# SUP_2_5_FMC.net
KiCad netlist of a schematic drawn in Altium Designer
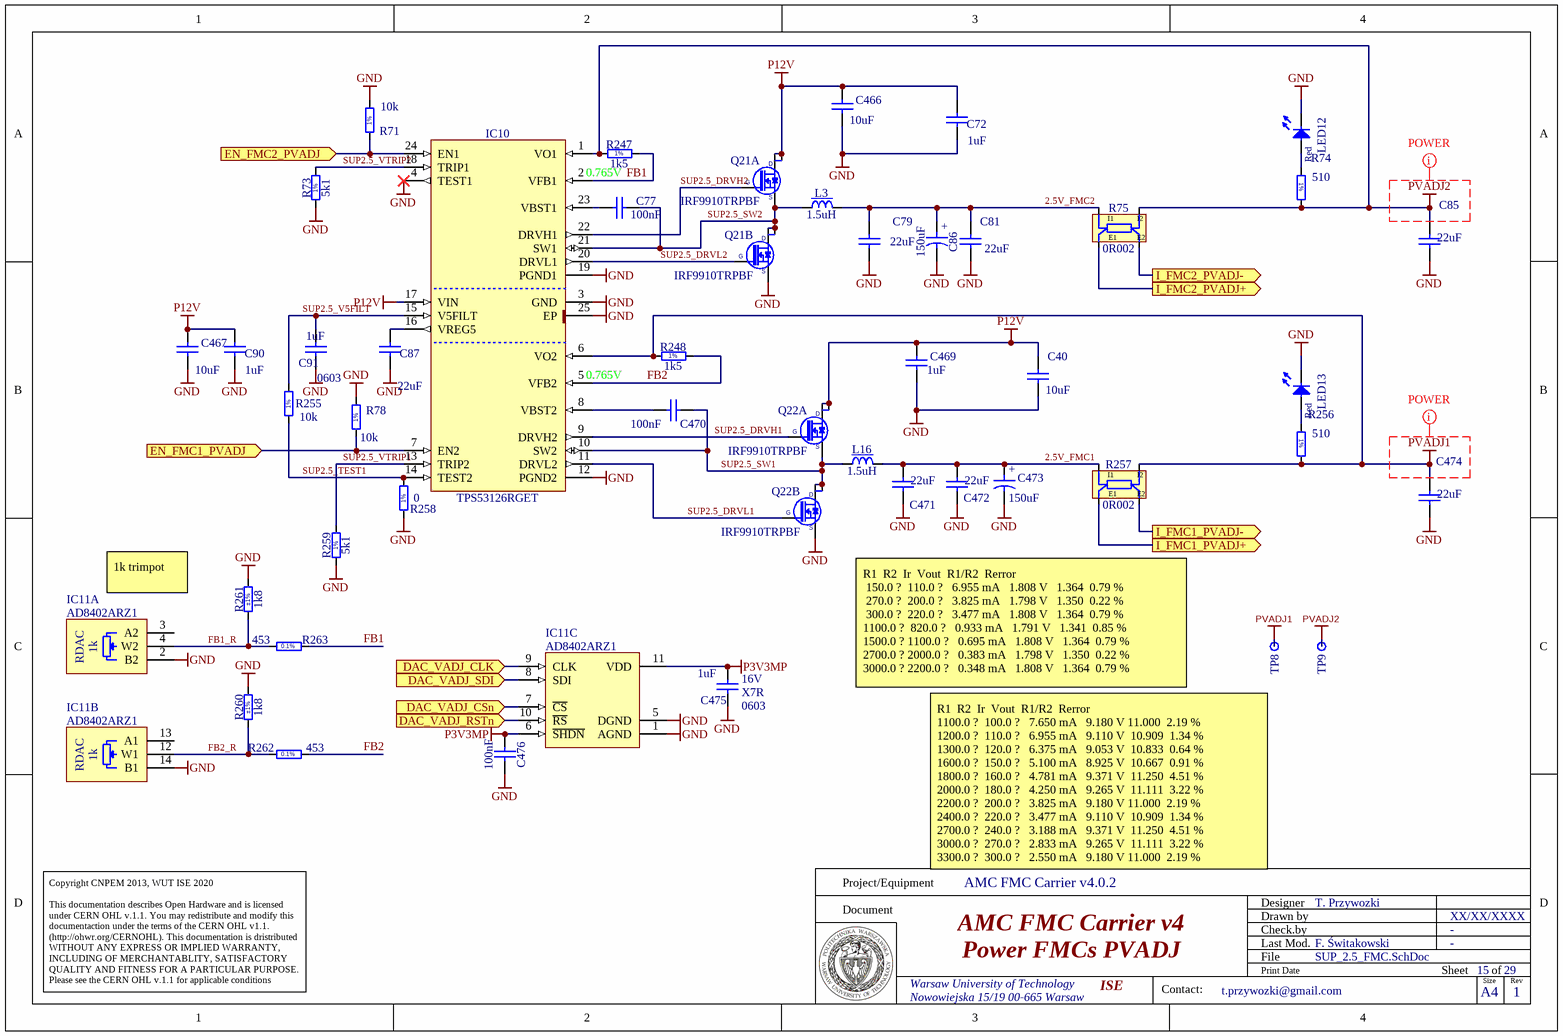
[diagram p0: SUP_2.5_FMC.SchDoc]

(export (version "E")
  (design (tool "Eeschema 10.0.6"))
  (components
    (comp (ref "C40")
      (value "10uF")
      (footprint "CAPC2012X135N")
      (description "Non-polarised capacitor")
      (fields
        (field (name "PART NUMBER") "CC0805_10UF_16V_10%_X5R")
        (field (name "VOLTAGE") "16V")
        (field (name "AUTHOR") "CERN DEM JLC")
      )
      (libsource (lib "Capacitors") (part "Capacitor - non polarized"))
    )
    (comp (ref "C72")
      (value "1uF")
      (footprint "CAPC1608X87N")
      (description "Non-polarised capacitor")
      (fields
        (field (name "PART NUMBER") "CC0603_1UF_16V_10%_X7R")
        (field (name "VOLTAGE") "16V")
        (field (name "AUTHOR") "CERN DEM JLC")
      )
      (libsource (lib "Capacitors") (part "Capacitor - non polarized"))
    )
    (comp (ref "C77")
      (value "100nF")
      (footprint "CAPC1005X55N")
      (description "Non-polarised capacitor")
      (fields
        (field (name "PART NUMBER") "CC0402_100NF_16V_10%_X7R")
        (field (name "VOLTAGE") "16V")
        (field (name "AUTHOR") "CERN DEM JLC")
      )
      (libsource (lib "Capacitors") (part "Capacitor - non polarized"))
    )
    (comp (ref "C79")
      (value "22uF")
      (footprint "CAPC3216X180N")
      (description "Non-polarised capacitor")
      (fields
        (field (name "PART NUMBER") "CC1206_22UF_10V_10%_X7R")
        (field (name "VOLTAGE") "10V")
        (field (name "AUTHOR") "CERN DEM JLC")
      )
      (libsource (lib "Capacitors") (part "Capacitor - non polarized"))
    )
    (comp (ref "C81")
      (value "22uF")
      (footprint "CAPC3216X180N")
      (description "Non-polarised capacitor")
      (fields
        (field (name "PART NUMBER") "CC1206_22UF_10V_10%_X7R")
        (field (name "VOLTAGE") "10V")
        (field (name "AUTHOR") "CERN DEM JLC")
      )
      (libsource (lib "Capacitors") (part "Capacitor - non polarized"))
    )
    (comp (ref "C85")
      (value "22uF")
      (footprint "CAPC3216X180N")
      (description "Non-polarised capacitor")
      (fields
        (field (name "PART NUMBER") "CC1206_22UF_10V_10%_X7R")
        (field (name "VOLTAGE") "10V")
        (field (name "AUTHOR") "CERN DEM JLC")
      )
      (libsource (lib "Capacitors") (part "Capacitor - non polarized"))
    )
    (comp (ref "C86")
      (value "150uF")
      (footprint "CAPMP7343X200N")
      (description "Polarised capacitor")
      (fields
        (field (name "PART NUMBER") "CAEM7343-20_150UF_4V_20%_LESR0016")
        (field (name "VOLTAGE") "4V")
        (field (name "AUTHOR") "CERN DEM JLC")
      )
      (libsource (lib "Capacitors") (part "Capacitor - polarized"))
    )
    (comp (ref "C87")
      (value "22uF")
      (footprint "CAPC3216X180N")
      (description "Non-polarised capacitor")
      (fields
        (field (name "PART NUMBER") "CC1206_22UF_10V_10%_X7R")
        (field (name "VOLTAGE") "10V")
        (field (name "AUTHOR") "CERN DEM JLC")
      )
      (libsource (lib "Capacitors") (part "Capacitor - non polarized"))
    )
    (comp (ref "C90")
      (value "1uF")
      (footprint "CAPC1608X87N")
      (description "Non-polarised capacitor")
      (fields
        (field (name "PART NUMBER") "CC0603_1UF_16V_10%_X7R")
        (field (name "VOLTAGE") "16V")
        (field (name "AUTHOR") "CERN DEM JLC")
      )
      (libsource (lib "Capacitors") (part "Capacitor - non polarized"))
    )
    (comp (ref "C91")
      (value "1uF")
      (footprint "CAPC1608X87N")
      (description "Non-polarised capacitor")
      (fields
        (field (name "PART NUMBER") "CC0603_1UF_16V_10%_X7R")
        (field (name "VOLTAGE") "16V")
        (field (name "CASE") "0603")
        (field (name "AUTHOR") "CERN DEM JLC")
      )
      (libsource (lib "Capacitors") (part "Capacitor - non polarized"))
    )
    (comp (ref "C466")
      (value "10uF")
      (footprint "CAPC2012X135N")
      (description "Non-polarised capacitor")
      (fields
        (field (name "PART NUMBER") "CC0805_10UF_16V_10%_X5R")
        (field (name "VOLTAGE") "16V")
        (field (name "AUTHOR") "CERN DEM JLC")
      )
      (libsource (lib "Capacitors") (part "Capacitor - non polarized"))
    )
    (comp (ref "C467")
      (value "10uF")
      (footprint "CAPC2012X135N")
      (description "Non-polarised capacitor")
      (fields
        (field (name "PART NUMBER") "CC0805_10UF_16V_10%_X5R")
        (field (name "VOLTAGE") "16V")
        (field (name "AUTHOR") "CERN DEM JLC")
      )
      (libsource (lib "Capacitors") (part "Capacitor - non polarized"))
    )
    (comp (ref "C469")
      (value "1uF")
      (footprint "CAPC1608X87N")
      (description "Non-polarised capacitor")
      (fields
        (field (name "PART NUMBER") "CC0603_1UF_16V_10%_X7R")
        (field (name "VOLTAGE") "16V")
        (field (name "AUTHOR") "CERN DEM JLC")
      )
      (libsource (lib "Capacitors") (part "Capacitor - non polarized"))
    )
    (comp (ref "C470")
      (value "100nF")
      (footprint "CAPC1005X55N")
      (description "Non-polarised capacitor")
      (fields
        (field (name "PART NUMBER") "CC0402_100NF_16V_10%_X7R")
        (field (name "VOLTAGE") "16V")
        (field (name "AUTHOR") "CERN DEM JLC")
      )
      (libsource (lib "Capacitors") (part "Capacitor - non polarized"))
    )
    (comp (ref "C471")
      (value "22uF")
      (footprint "CAPC3216X180N")
      (description "Non-polarised capacitor")
      (fields
        (field (name "PART NUMBER") "CC1206_22UF_10V_10%_X7R")
        (field (name "VOLTAGE") "10V")
        (field (name "AUTHOR") "CERN DEM JLC")
      )
      (libsource (lib "Capacitors") (part "Capacitor - non polarized"))
    )
    (comp (ref "C472")
      (value "22uF")
      (footprint "CAPC3216X180N")
      (description "Non-polarised capacitor")
      (fields
        (field (name "PART NUMBER") "CC1206_22UF_10V_10%_X7R")
        (field (name "VOLTAGE") "10V")
        (field (name "AUTHOR") "CERN DEM JLC")
      )
      (libsource (lib "Capacitors") (part "Capacitor - non polarized"))
    )
    (comp (ref "C473")
      (value "150uF")
      (footprint "CAPMP7343X200N")
      (description "Polarised capacitor")
      (fields
        (field (name "PART NUMBER") "CAEM7343-20_150UF_4V_20%_LESR0016")
        (field (name "VOLTAGE") "4V")
        (field (name "AUTHOR") "CERN DEM JLC")
      )
      (libsource (lib "Capacitors") (part "Capacitor - polarized"))
    )
    (comp (ref "C474")
      (value "22uF")
      (footprint "CAPC3216X180N")
      (description "Non-polarised capacitor")
      (fields
        (field (name "PART NUMBER") "CC1206_22UF_10V_10%_X7R")
        (field (name "VOLTAGE") "10V")
        (field (name "AUTHOR") "CERN DEM JLC")
      )
      (libsource (lib "Capacitors") (part "Capacitor - non polarized"))
    )
    (comp (ref "C475")
      (value "1uF")
      (footprint "CAPC1608X87N")
      (description "Non-polarised capacitor")
      (fields
        (field (name "PART NUMBER") "CC0603_1UF_16V_10%_X7R")
        (field (name "VOLTAGE") "16V")
        (field (name "TC") "X7R")
        (field (name "TOLERANCE") "±10%")
        (field (name "CASE") "0603")
        (field (name "AUTHOR") "CERN DEM JLC")
      )
      (libsource (lib "Capacitors") (part "Capacitor - non polarized"))
    )
    (comp (ref "C476")
      (value "100nF")
      (footprint "CAPC0603X33N")
      (description "Non-polarised capacitor")
      (fields
        (field (name "PART NUMBER") "CC0201_100NF_6.3V_10%_X5R")
        (field (name "VOLTAGE") "6.3V")
        (field (name "AUTHOR") "CERN DEM JLC")
      )
      (libsource (lib "Capacitors") (part "Capacitor - non polarized"))
    )
    (comp (ref "IC10")
      (value "TPS53126RGET")
      (footprint "QFN50P400X400X100-25N-S255")
      (description "Dual Synchronous Step-Down Controller For Low Voltage Power Rails")
      (fields (field (name "MANUFACTURER") "TEXAS INSTRUMENTS") (field (name "AUTHOR") "CERN DEM JLC"))
      (libsource (lib "ICs And Semiconductors") (part "TPS53126RGET"))
    )
    (comp (ref "IC11")
      (value "AD8402ARZ1")
      (footprint "SOIC127P600X175-14N")
      (description "2-Channel 1k Digital Potentiometer")
      (fields (field (name "MANUFACTURER") "ANALOG DEVICES") (field (name "AUTHOR") "CERN DEM JLC"))
      (libsource (lib "ICs And Semiconductors") (part "AD8402ARZ1"))
    )
    (comp (ref "L3")
      (value "1.5uH")
      (footprint "IND_TDK_SPM6530")
      (description "Inductor With Core")
      (fields
        (field (name "PART NUMBER") "IND_1.5UH_20%_TDK_SPM6530")
        (field (name "POWER") "11A")
        (field (name "AUTHOR") "CERN DEM MR")
      )
      (libsource (lib "Inductors & Transformers") (part "Inductor With Magnetic core"))
    )
    (comp (ref "L16")
      (value "1.5uH")
      (footprint "IND_TDK_SPM6530")
      (description "Inductor With Core")
      (fields
        (field (name "PART NUMBER") "IND_1.5UH_20%_TDK_SPM6530")
        (field (name "POWER") "11A")
        (field (name "AUTHOR") "CERN DEM MR")
      )
      (libsource (lib "Inductors & Transformers") (part "Inductor With Magnetic core"))
    )
    (comp (ref "LED12")
      (value "Red")
      (footprint "LED_KINGBRIGHT_KPH-1608SURCK")
      (description "LED Red 1C 2A")
      (fields
        (field (name "PART NUMBER") "LED_KINGBRIGHT_KPH-1608SURCK")
        (field (name "MANUFACTURER") "KINGBRIGHT")
        (field (name "AUTHOR") "CERN DEM JLC")
      )
      (libsource (lib "ICs And Semiconductors") (part "LED Red 1C 2A"))
    )
    (comp (ref "LED13")
      (value "Red")
      (footprint "LED_KINGBRIGHT_KPH-1608SURCK")
      (description "LED Red 1C 2A")
      (fields
        (field (name "PART NUMBER") "LED_KINGBRIGHT_KPH-1608SURCK")
        (field (name "MANUFACTURER") "KINGBRIGHT")
        (field (name "AUTHOR") "CERN DEM JLC")
      )
      (libsource (lib "ICs And Semiconductors") (part "LED Red 1C 2A"))
    )
    (comp (ref "Q21")
      (value "IRF9910TRPBF")
      (footprint "SOIC127P600X175-8N")
      (description "Dual SO-8 MOSFET For POL Cconverter")
      (fields (field (name "MANUFACTURER") "INTERNATIONAL RECTIFIER") (field (name "AUTHOR") "TP"))
      (libsource (lib "AMC_FMC_Carrier") (part "IRF9910"))
    )
    (comp (ref "Q22")
      (value "IRF9910TRPBF")
      (footprint "SOIC127P600X175-8N")
      (description "Dual SO-8 MOSFET For POL Cconverter")
      (fields (field (name "MANUFACTURER") "INTERNATIONAL RECTIFIER") (field (name "AUTHOR") "TP"))
      (libsource (lib "AMC_FMC_Carrier") (part "IRF9910"))
    )
    (comp (ref "R71")
      (value "10k")
      (footprint "RESC1005X40N")
      (description "Resistor - 1%")
      (fields
        (field (name "PART NUMBER") "R0402_10K_1%_0.0625W_100PPM")
        (field (name "POWER") "0.0625W")
        (field (name "AUTHOR") "CERN DEM JLC")
      )
      (libsource (lib "Resistors") (part "Resistor - 1%"))
    )
    (comp (ref "R73")
      (value "5k1")
      (footprint "RESC1608X55N")
      (description "Resistor - 1%")
      (fields
        (field (name "PART NUMBER") "R0603_5K1_1%_0.1W_100PPM")
        (field (name "POWER") "0.1W")
        (field (name "AUTHOR") "CERN DEM JLC")
      )
      (libsource (lib "Resistors") (part "Resistor - 1%"))
    )
    (comp (ref "R74")
      (value "510")
      (footprint "RESC1005X40N")
      (description "Resistor - 1%")
      (fields
        (field (name "PART NUMBER") "R0402_510R_1%_0.0625W_100PPM")
        (field (name "POWER") "0.0625W")
        (field (name "AUTHOR") "CERN DEM JLC")
      )
      (libsource (lib "Resistors") (part "Resistor - 1%"))
    )
    (comp (ref "R75")
      (value "0R002")
      (footprint "RES_VISHAY_WSK2512_0R005-0R2")
      (description "Power and Current Sensing Resistor")
      (fields
        (field (name "PART NUMBER") "R2512_0R002_1%_1W_35PPM_VISHAY_WSK")
        (field (name "POWER") "1W")
        (field (name "AUTHOR") "CERN DEM MR")
      )
      (libsource (lib "Resistors") (part "Current Sense Resistor"))
    )
    (comp (ref "R78")
      (value "10k")
      (footprint "RESC1005X40N")
      (description "Resistor - 1%")
      (fields
        (field (name "PART NUMBER") "R0402_10K_1%_0.0625W_100PPM")
        (field (name "POWER") "0.0625W")
        (field (name "AUTHOR") "CERN DEM JLC")
      )
      (libsource (lib "Resistors") (part "Resistor - 1%"))
    )
    (comp (ref "R247")
      (value "1k5")
      (footprint "RESC1608X55N")
      (description "Resistor - 1%")
      (fields
        (field (name "PART NUMBER") "R0603_1K5_1%_0.1W_100PPM")
        (field (name "POWER") "0.1W")
        (field (name "AUTHOR") "CERN DEM JLC")
      )
      (libsource (lib "Resistors") (part "Resistor - 1%"))
    )
    (comp (ref "R248")
      (value "1k5")
      (footprint "RESC1608X55N")
      (description "Resistor - 1%")
      (fields
        (field (name "PART NUMBER") "R0603_1K5_1%_0.1W_100PPM")
        (field (name "POWER") "0.1W")
        (field (name "AUTHOR") "CERN DEM JLC")
      )
      (libsource (lib "Resistors") (part "Resistor - 1%"))
    )
    (comp (ref "R255")
      (value "10k")
      (footprint "RESC1005X40N")
      (description "Resistor - 1%")
      (fields
        (field (name "PART NUMBER") "R0402_10K_1%_0.0625W_100PPM")
        (field (name "POWER") "0.0625W")
        (field (name "AUTHOR") "CERN DEM JLC")
      )
      (libsource (lib "Resistors") (part "Resistor - 1%"))
    )
    (comp (ref "R256")
      (value "510")
      (footprint "RESC1005X40N")
      (description "Resistor - 1%")
      (fields
        (field (name "PART NUMBER") "R0402_510R_1%_0.0625W_100PPM")
        (field (name "POWER") "0.0625W")
        (field (name "AUTHOR") "CERN DEM JLC")
      )
      (libsource (lib "Resistors") (part "Resistor - 1%"))
    )
    (comp (ref "R257")
      (value "0R002")
      (footprint "RES_VISHAY_WSK2512_0R005-0R2")
      (description "Power and Current Sensing Resistor")
      (fields
        (field (name "PART NUMBER") "R2512_0R002_1%_1W_35PPM_VISHAY_WSK")
        (field (name "POWER") "1W")
        (field (name "AUTHOR") "CERN DEM MR")
      )
      (libsource (lib "Resistors") (part "Current Sense Resistor"))
    )
    (comp (ref "R258")
      (value "0")
      (footprint "RESC1005X40N")
      (description "Resistor - 1%")
      (fields
        (field (name "PART NUMBER") "R0402_0R_JUMPER")
        (field (name "MANUFACTURER") "GENERIC")
        (field (name "AUTHOR") "CERN DEM JLC")
      )
      (libsource (lib "Resistors") (part "Resistor - 1%"))
    )
    (comp (ref "R259")
      (value "5k1")
      (footprint "RESC1608X55N")
      (description "Resistor - 1%")
      (fields
        (field (name "PART NUMBER") "R0603_5K1_1%_0.1W_100PPM")
        (field (name "POWER") "0.1W")
        (field (name "AUTHOR") "CERN DEM JLC")
      )
      (libsource (lib "Resistors") (part "Resistor - 1%"))
    )
    (comp (ref "R260")
      (value "1k8")
      (footprint "RESC1608X55N")
      (description "Resistor - 1%")
      (fields
        (field (name "TOLERANCE") "±1%")
        (field (name "PART NUMBER") "R0603_1K8_1%_0.1W_100PPM")
        (field (name "POWER") "0.1W")
        (field (name "AUTHOR") "CERN DEM JLC")
      )
      (libsource (lib "Resistors") (part "Resistor - 1%"))
    )
    (comp (ref "R261")
      (value "1k8")
      (footprint "RESC1608X55N")
      (description "Resistor - 1%")
      (fields
        (field (name "TOLERANCE") "±1%")
        (field (name "PART NUMBER") "R0603_1K8_1%_0.1W_100PPM")
        (field (name "POWER") "0.1W")
        (field (name "AUTHOR") "CERN DEM JLC")
      )
      (libsource (lib "Resistors") (part "Resistor - 1%"))
    )
    (comp (ref "R262")
      (value "453")
      (footprint "RESC1608X55N")
      (description "Resistor - 0.1%")
      (fields
        (field (name "PART NUMBER") "R0603_453R_0.1%_0.063W_10PPM")
        (field (name "POWER") "0.063W")
        (field (name "AUTHOR") "CERN DEM JLC")
      )
      (libsource (lib "Resistors") (part "Resistor - 0.1%"))
    )
    (comp (ref "R263")
      (value "453")
      (footprint "RESC1608X55N")
      (description "Resistor - 0.1%")
      (fields
        (field (name "PART NUMBER") "R0603_453R_0.1%_0.063W_10PPM")
        (field (name "POWER") "0.063W")
        (field (name "AUTHOR") "CERN DEM JLC")
      )
      (libsource (lib "Resistors") (part "Resistor - 0.1%"))
    )
    (comp (ref "TP8")
      (value "Test Point")
      (footprint "TPS127")
      (fields (field (name "PART NUMBER") "SMD_PAD_1.27X1.27MM") (field (name "AUTHOR") "CERN DEM JLC"))
      (libsource (lib "Eletro-mechanical") (part "Test Point"))
    )
    (comp (ref "TP9")
      (value "Test Point")
      (footprint "TPS127")
      (fields (field (name "PART NUMBER") "SMD_PAD_1.27X1.27MM") (field (name "AUTHOR") "CERN DEM JLC"))
      (libsource (lib "Eletro-mechanical") (part "Test Point"))
    )
  )
  (nets
    (net (code "1") (name "/2.5V_FMC1") (class "Default")
      (node (ref "C471") (pin "1") (pinfunction "1_1") (pintype "passive"))
      (node (ref "C472") (pin "1") (pinfunction "1_1") (pintype "passive"))
      (node (ref "C473") (pin "1") (pinfunction "1_1") (pintype "passive"))
      (node (ref "L16") (pin "2") (pinfunction "2_2") (pintype "passive"))
      (node (ref "R257") (pin "I1") (pinfunction "I1_I1") (pintype "passive"))
    )
    (net (code "2") (name "/2.5V_FMC2") (class "Default")
      (node (ref "C79") (pin "1") (pinfunction "1_1") (pintype "passive"))
      (node (ref "C81") (pin "1") (pinfunction "1_1") (pintype "passive"))
      (node (ref "C86") (pin "1") (pinfunction "1_1") (pintype "passive"))
      (node (ref "L3") (pin "2") (pinfunction "2_2") (pintype "passive"))
      (node (ref "R75") (pin "I1") (pinfunction "I1_I1") (pintype "passive"))
    )
    (net (code "3") (name "/DAC_VADJ_CLK") (class "Default")
      (node (ref "IC11") (pin "9") (pinfunction "CLK_9") (pintype "input"))
    )
    (net (code "4") (name "/DAC_VADJ_CSn") (class "Default")
      (node (ref "IC11") (pin "7") (pinfunction "~{CS}_7") (pintype "input"))
    )
    (net (code "5") (name "/DAC_VADJ_RSTn") (class "Default")
      (node (ref "IC11") (pin "10") (pinfunction "~{RS}_10") (pintype "input"))
    )
    (net (code "6") (name "/DAC_VADJ_SDI") (class "Default")
      (node (ref "IC11") (pin "8") (pinfunction "SDI_8") (pintype "input"))
    )
    (net (code "7") (name "/EN_FMC1_PVADJ") (class "Default")
      (node (ref "IC10") (pin "7") (pinfunction "EN2_7") (pintype "input"))
      (node (ref "R78") (pin "1") (pinfunction "1_1") (pintype "passive"))
    )
    (net (code "8") (name "/EN_FMC2_PVADJ") (class "Default")
      (node (ref "IC10") (pin "24") (pinfunction "EN1_24") (pintype "input"))
      (node (ref "R71") (pin "1") (pinfunction "1_1") (pintype "passive"))
    )
    (net (code "9") (name "/FB1") (class "Default")
      (node (ref "IC10") (pin "2") (pinfunction "VFB1_2") (pintype "input"))
      (node (ref "R247") (pin "2") (pinfunction "2_2") (pintype "passive"))
      (node (ref "R263") (pin "1") (pinfunction "1_1") (pintype "passive"))
    )
    (net (code "10") (name "/FB1_R") (class "Default")
      (node (ref "IC11") (pin "4") (pinfunction "W2_4") (pintype "passive"))
      (node (ref "R261") (pin "1") (pinfunction "1_1") (pintype "passive"))
      (node (ref "R263") (pin "2") (pinfunction "2_2") (pintype "passive"))
    )
    (net (code "11") (name "/FB2") (class "Default")
      (node (ref "IC10") (pin "5") (pinfunction "VFB2_5") (pintype "input"))
      (node (ref "R248") (pin "2") (pinfunction "2_2") (pintype "passive"))
      (node (ref "R262") (pin "2") (pinfunction "2_2") (pintype "passive"))
    )
    (net (code "12") (name "/FB2_R") (class "Default")
      (node (ref "IC11") (pin "12") (pinfunction "W1_12") (pintype "passive"))
      (node (ref "R260") (pin "1") (pinfunction "1_1") (pintype "passive"))
      (node (ref "R262") (pin "1") (pinfunction "1_1") (pintype "passive"))
    )
    (net (code "13") (name "/I_FMC1_PVADJ+") (class "Default")
      (node (ref "R257") (pin "E1") (pinfunction "E1_E1") (pintype "passive"))
    )
    (net (code "14") (name "/I_FMC1_PVADJ-") (class "Default")
      (node (ref "R257") (pin "E2") (pinfunction "E2_E2") (pintype "passive"))
    )
    (net (code "15") (name "/I_FMC2_PVADJ+") (class "Default")
      (node (ref "R75") (pin "E1") (pinfunction "E1_E1") (pintype "passive"))
    )
    (net (code "16") (name "/I_FMC2_PVADJ-") (class "Default")
      (node (ref "R75") (pin "E2") (pinfunction "E2_E2") (pintype "passive"))
    )
    (net (code "17") (name "/SUP2.5_DRVH1") (class "Default")
      (node (ref "IC10") (pin "9") (pinfunction "DRVH2_9") (pintype "output"))
      (node (ref "Q22") (pin "4") (pinfunction "G_4") (pintype "passive"))
    )
    (net (code "18") (name "/SUP2.5_DRVH2") (class "Default")
      (node (ref "IC10") (pin "22") (pinfunction "DRVH1_22") (pintype "output"))
      (node (ref "Q21") (pin "4") (pinfunction "G_4") (pintype "passive"))
    )
    (net (code "19") (name "/SUP2.5_DRVL1") (class "Default")
      (node (ref "IC10") (pin "11") (pinfunction "DRVL2_11") (pintype "output"))
      (node (ref "Q22") (pin "2") (pinfunction "G_2") (pintype "passive"))
    )
    (net (code "20") (name "/SUP2.5_DRVL2") (class "Default")
      (node (ref "IC10") (pin "20") (pinfunction "DRVL1_20") (pintype "output"))
      (node (ref "Q21") (pin "2") (pinfunction "G_2") (pintype "passive"))
    )
    (net (code "21") (name "/SUP2.5_SW1") (class "Default")
      (node (ref "C470") (pin "1") (pinfunction "1_1") (pintype "passive"))
      (node (ref "IC10") (pin "10") (pinfunction "SW2_10") (pintype "bidirectional"))
      (node (ref "L16") (pin "1") (pinfunction "1_1") (pintype "passive"))
      (node (ref "Q22") (pin "3") (pinfunction "S_3") (pintype "passive"))
      (node (ref "Q22") (pin "7") (pinfunction "D_7") (pintype "passive"))
      (node (ref "Q22") (pin "8") (pinfunction "D_8") (pintype "passive"))
    )
    (net (code "22") (name "/SUP2.5_SW2") (class "Default")
      (node (ref "C77") (pin "1") (pinfunction "1_1") (pintype "passive"))
      (node (ref "IC10") (pin "21") (pinfunction "SW1_21") (pintype "bidirectional"))
      (node (ref "L3") (pin "1") (pinfunction "1_1") (pintype "passive"))
      (node (ref "Q21") (pin "3") (pinfunction "S_3") (pintype "passive"))
      (node (ref "Q21") (pin "7") (pinfunction "D_7") (pintype "passive"))
      (node (ref "Q21") (pin "8") (pinfunction "D_8") (pintype "passive"))
    )
    (net (code "23") (name "/SUP2.5_TEST1") (class "Default")
      (node (ref "IC10") (pin "14") (pinfunction "TEST2_14") (pintype "input"))
      (node (ref "R255") (pin "1") (pinfunction "1_1") (pintype "passive"))
      (node (ref "R258") (pin "2") (pinfunction "2_2") (pintype "passive"))
    )
    (net (code "24") (name "/SUP2.5_V5FILT") (class "Default")
      (node (ref "C91") (pin "2") (pinfunction "2_2") (pintype "passive"))
      (node (ref "IC10") (pin "15") (pinfunction "V5FILT_15") (pintype "input"))
      (node (ref "R255") (pin "2") (pinfunction "2_2") (pintype "passive"))
    )
    (net (code "25") (name "/SUP2.5_VTRIP1") (class "Default")
      (node (ref "IC10") (pin "13") (pinfunction "TRIP2_13") (pintype "input"))
      (node (ref "R259") (pin "2") (pinfunction "2_2") (pintype "passive"))
    )
    (net (code "26") (name "/SUP2.5_VTRIP2") (class "Default")
      (node (ref "IC10") (pin "18") (pinfunction "TRIP1_18") (pintype "input"))
      (node (ref "R73") (pin "2") (pinfunction "2_2") (pintype "passive"))
    )
    (net (code "27") (name "GND") (class "Default")
      (node (ref "C40") (pin "1") (pinfunction "1_1") (pintype "passive"))
      (node (ref "C466") (pin "1") (pinfunction "1_1") (pintype "passive"))
      (node (ref "C467") (pin "1") (pinfunction "1_1") (pintype "passive"))
      (node (ref "C469") (pin "1") (pinfunction "1_1") (pintype "passive"))
      (node (ref "C471") (pin "2") (pinfunction "2_2") (pintype "passive"))
      (node (ref "C472") (pin "2") (pinfunction "2_2") (pintype "passive"))
      (node (ref "C473") (pin "2") (pinfunction "2_2") (pintype "passive"))
      (node (ref "C474") (pin "2") (pinfunction "2_2") (pintype "passive"))
      (node (ref "C475") (pin "1") (pinfunction "1_1") (pintype "passive"))
      (node (ref "C476") (pin "2") (pinfunction "2_2") (pintype "passive"))
      (node (ref "C72") (pin "1") (pinfunction "1_1") (pintype "passive"))
      (node (ref "C79") (pin "2") (pinfunction "2_2") (pintype "passive"))
      (node (ref "C81") (pin "2") (pinfunction "2_2") (pintype "passive"))
      (node (ref "C85") (pin "2") (pinfunction "2_2") (pintype "passive"))
      (node (ref "C86") (pin "2") (pinfunction "2_2") (pintype "passive"))
      (node (ref "C87") (pin "1") (pinfunction "1_1") (pintype "passive"))
      (node (ref "C90") (pin "1") (pinfunction "1_1") (pintype "passive"))
      (node (ref "C91") (pin "1") (pinfunction "1_1") (pintype "passive"))
      (node (ref "IC10") (pin "12") (pinfunction "PGND2_12") (pintype "power_in"))
      (node (ref "IC10") (pin "19") (pinfunction "PGND1_19") (pintype "power_in"))
      (node (ref "IC10") (pin "25") (pinfunction "EP_25") (pintype "power_in"))
      (node (ref "IC10") (pin "3") (pinfunction "GND_3") (pintype "power_in"))
      (node (ref "IC10") (pin "4") (pinfunction "TEST1_4") (pintype "output"))
      (node (ref "IC11") (pin "1") (pinfunction "AGND_1") (pintype "power_in"))
      (node (ref "IC11") (pin "14") (pinfunction "B1_14") (pintype "passive"))
      (node (ref "IC11") (pin "2") (pinfunction "B2_2") (pintype "passive"))
      (node (ref "IC11") (pin "5") (pinfunction "DGND_5") (pintype "power_in"))
      (node (ref "LED12") (pin "1") (pinfunction "C_1") (pintype "passive"))
      (node (ref "LED13") (pin "1") (pinfunction "C_1") (pintype "passive"))
      (node (ref "Q21") (pin "1") (pinfunction "S_1") (pintype "passive"))
      (node (ref "Q22") (pin "1") (pinfunction "S_1") (pintype "passive"))
      (node (ref "R258") (pin "1") (pinfunction "1_1") (pintype "passive"))
      (node (ref "R259") (pin "1") (pinfunction "1_1") (pintype "passive"))
      (node (ref "R260") (pin "2") (pinfunction "2_2") (pintype "passive"))
      (node (ref "R261") (pin "2") (pinfunction "2_2") (pintype "passive"))
      (node (ref "R71") (pin "2") (pinfunction "2_2") (pintype "passive"))
      (node (ref "R73") (pin "1") (pinfunction "1_1") (pintype "passive"))
      (node (ref "R78") (pin "2") (pinfunction "2_2") (pintype "passive"))
    )
    (net (code "28") (name "Net-(IC10-VBST1)") (class "Default")
      (node (ref "C77") (pin "2") (pinfunction "2_2") (pintype "passive"))
      (node (ref "IC10") (pin "23") (pinfunction "VBST1_23") (pintype "input"))
    )
    (net (code "29") (name "Net-(IC10-VBST2)") (class "Default")
      (node (ref "C470") (pin "2") (pinfunction "2_2") (pintype "passive"))
      (node (ref "IC10") (pin "8") (pinfunction "VBST2_8") (pintype "input"))
    )
    (net (code "30") (name "Net-(IC10-VREG5)") (class "Default")
      (node (ref "C87") (pin "2") (pinfunction "2_2") (pintype "passive"))
      (node (ref "IC10") (pin "16") (pinfunction "VREG5_16") (pintype "output"))
    )
    (net (code "31") (name "Net-(LED12-A)") (class "Default")
      (node (ref "LED12") (pin "2") (pinfunction "A_2") (pintype "passive"))
      (node (ref "R74") (pin "1") (pinfunction "1_1") (pintype "passive"))
    )
    (net (code "32") (name "Net-(LED13-A)") (class "Default")
      (node (ref "LED13") (pin "2") (pinfunction "A_2") (pintype "passive"))
      (node (ref "R256") (pin "1") (pinfunction "1_1") (pintype "passive"))
    )
    (net (code "33") (name "P3V3MP") (class "Default")
      (node (ref "C475") (pin "2") (pinfunction "2_2") (pintype "passive"))
      (node (ref "C476") (pin "1") (pinfunction "1_1") (pintype "passive"))
      (node (ref "IC11") (pin "11") (pinfunction "VDD_11") (pintype "power_in"))
      (node (ref "IC11") (pin "6") (pinfunction "~{SHDN}_6") (pintype "input"))
    )
    (net (code "34") (name "P12V") (class "Default")
      (node (ref "C40") (pin "2") (pinfunction "2_2") (pintype "passive"))
      (node (ref "C466") (pin "2") (pinfunction "2_2") (pintype "passive"))
      (node (ref "C467") (pin "2") (pinfunction "2_2") (pintype "passive"))
      (node (ref "C469") (pin "2") (pinfunction "2_2") (pintype "passive"))
      (node (ref "C72") (pin "2") (pinfunction "2_2") (pintype "passive"))
      (node (ref "C90") (pin "2") (pinfunction "2_2") (pintype "passive"))
      (node (ref "IC10") (pin "17") (pinfunction "VIN_17") (pintype "input"))
      (node (ref "Q21") (pin "5") (pinfunction "D_5") (pintype "passive"))
      (node (ref "Q21") (pin "6") (pinfunction "D_6") (pintype "passive"))
      (node (ref "Q22") (pin "5") (pinfunction "D_5") (pintype "passive"))
      (node (ref "Q22") (pin "6") (pinfunction "D_6") (pintype "passive"))
    )
    (net (code "35") (name "PVADJ1") (class "Default")
      (node (ref "C474") (pin "1") (pinfunction "1_1") (pintype "passive"))
      (node (ref "IC10") (pin "6") (pinfunction "VO2_6") (pintype "input"))
      (node (ref "R248") (pin "1") (pinfunction "1_1") (pintype "passive"))
      (node (ref "R256") (pin "2") (pinfunction "2_2") (pintype "passive"))
      (node (ref "R257") (pin "I2") (pinfunction "I2_I2") (pintype "passive"))
      (node (ref "TP8") (pin "1") (pinfunction "1_1") (pintype "bidirectional"))
    )
    (net (code "36") (name "PVADJ2") (class "Default")
      (node (ref "C85") (pin "1") (pinfunction "1_1") (pintype "passive"))
      (node (ref "IC10") (pin "1") (pinfunction "VO1_1") (pintype "input"))
      (node (ref "R247") (pin "1") (pinfunction "1_1") (pintype "passive"))
      (node (ref "R74") (pin "2") (pinfunction "2_2") (pintype "passive"))
      (node (ref "R75") (pin "I2") (pinfunction "I2_I2") (pintype "passive"))
      (node (ref "TP9") (pin "1") (pinfunction "1_1") (pintype "bidirectional"))
    )
    (net (code "37") (name "unconnected-(IC11A-A2-Pad3)") (class "Default")
      (node (ref "IC11") (pin "3") (pinfunction "A2_3") (pintype "passive"))
    )
    (net (code "38") (name "unconnected-(IC11B-A1-Pad13)") (class "Default")
      (node (ref "IC11") (pin "13") (pinfunction "A1_13") (pintype "passive"))
    )
  )
)
